# SRD-05VDC-SL-C.net
KiCad netlist of a schematic drawn in Altium Designer
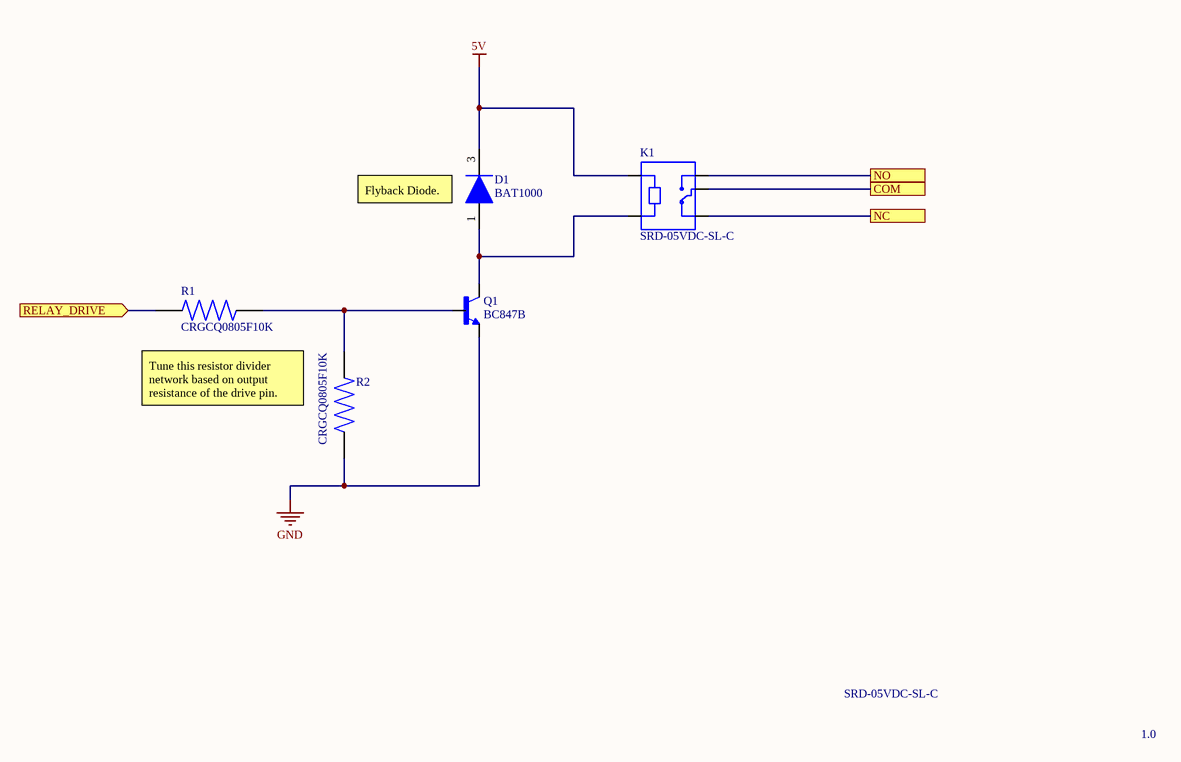
[diagram p0: SRD-05VDC-SL-C.SchDoc]

(export (version "E")
  (design (tool "Eeschema 10.0.6"))
  (components
    (comp (ref "D1")
      (value "BAT1000")
      (footprint "SOT91P240X110-3N")
      (description "Diode Schottky 40V 1A Surface Mount SOT-23-3")
      (fields (field (name "MF") "Diodes Inc."))
      (libsource (lib "BAT1000") (part "BAT1000"))
    )
    (comp (ref "K1")
      (value "SRD-05VDC-SL-C")
      (footprint "RELAY_SRD-05VDC-SL-C")
      (fields (field (name "MF") "Songle Relay"))
      (libsource (lib "SRD-05VDC-SL-C") (part "SRD-05VDC-SL-C"))
    )
    (comp (ref "Q1")
      (value "BC847B")
      (footprint "SOT100P230X110-3N")
      (description "Bipolar (BJT) Transistor NPN 45V 100mA 100MHz 150mW Surface Mount SOT-523")
      (fields (field (name "MF") "STMicroelectronics"))
      (libsource (lib "BC847B") (part "BC847B"))
    )
    (comp (ref "R1")
      (value "CRGCQ0805F10K")
      (footprint "RESC2012X65N")
      (description "Fixed Resistor CRGCQ 0805 10K 1%")
      (fields (field (name "MP") "CRGCQ0805F2K2") (field (name "MF") "TE Connectivity"))
      (libsource (lib "CRGCQ0805F10K") (part "CRGCQ0805F10K"))
    )
    (comp (ref "R2")
      (value "CRGCQ0805F10K")
      (footprint "RESC2012X65N")
      (description "Fixed Resistor CRGCQ 0805 10K 1%")
      (fields (field (name "MF") "TE Connectivity"))
      (libsource (lib "CRGCQ0805F10K") (part "CRGCQ0805F10K"))
    )
  )
  (nets
    (net (code "1") (name "/COM") (class "Default")
      (node (ref "K1") (pin "COM") (pinfunction "COM_COM") (pintype "passive"))
    )
    (net (code "2") (name "/NC") (class "Default")
      (node (ref "K1") (pin "NC") (pinfunction "NC_NC") (pintype "passive"))
    )
    (net (code "3") (name "/NO") (class "Default")
      (node (ref "K1") (pin "NO") (pinfunction "NO_NO") (pintype "passive"))
    )
    (net (code "4") (name "/RELAY_DRIVE") (class "Default")
      (node (ref "R1") (pin "1") (pinfunction "1_1") (pintype "passive"))
    )
    (net (code "5") (name "5V") (class "Default")
      (node (ref "D1") (pin "3") (pinfunction "CATHODE_3") (pintype "passive"))
      (node (ref "K1") (pin "A1") (pinfunction "A1_A1") (pintype "passive"))
    )
    (net (code "6") (name "GND") (class "Default")
      (node (ref "Q1") (pin "2") (pinfunction "E_2") (pintype "passive"))
      (node (ref "R2") (pin "1") (pinfunction "1_1") (pintype "passive"))
    )
    (net (code "7") (name "Net-(D1-ANODE)") (class "Default")
      (node (ref "D1") (pin "1") (pinfunction "ANODE_1") (pintype "passive"))
      (node (ref "K1") (pin "A2") (pinfunction "A2_A2") (pintype "passive"))
      (node (ref "Q1") (pin "3") (pinfunction "C_3") (pintype "passive"))
    )
    (net (code "8") (name "Net-(Q1-B)") (class "Default")
      (node (ref "Q1") (pin "1") (pinfunction "B_1") (pintype "passive"))
      (node (ref "R1") (pin "2") (pinfunction "2_2") (pintype "passive"))
      (node (ref "R2") (pin "2") (pinfunction "2_2") (pintype "passive"))
    )
  )
)
